# ProtoBoard.net
KiCad netlist of a schematic drawn in Altium Designer
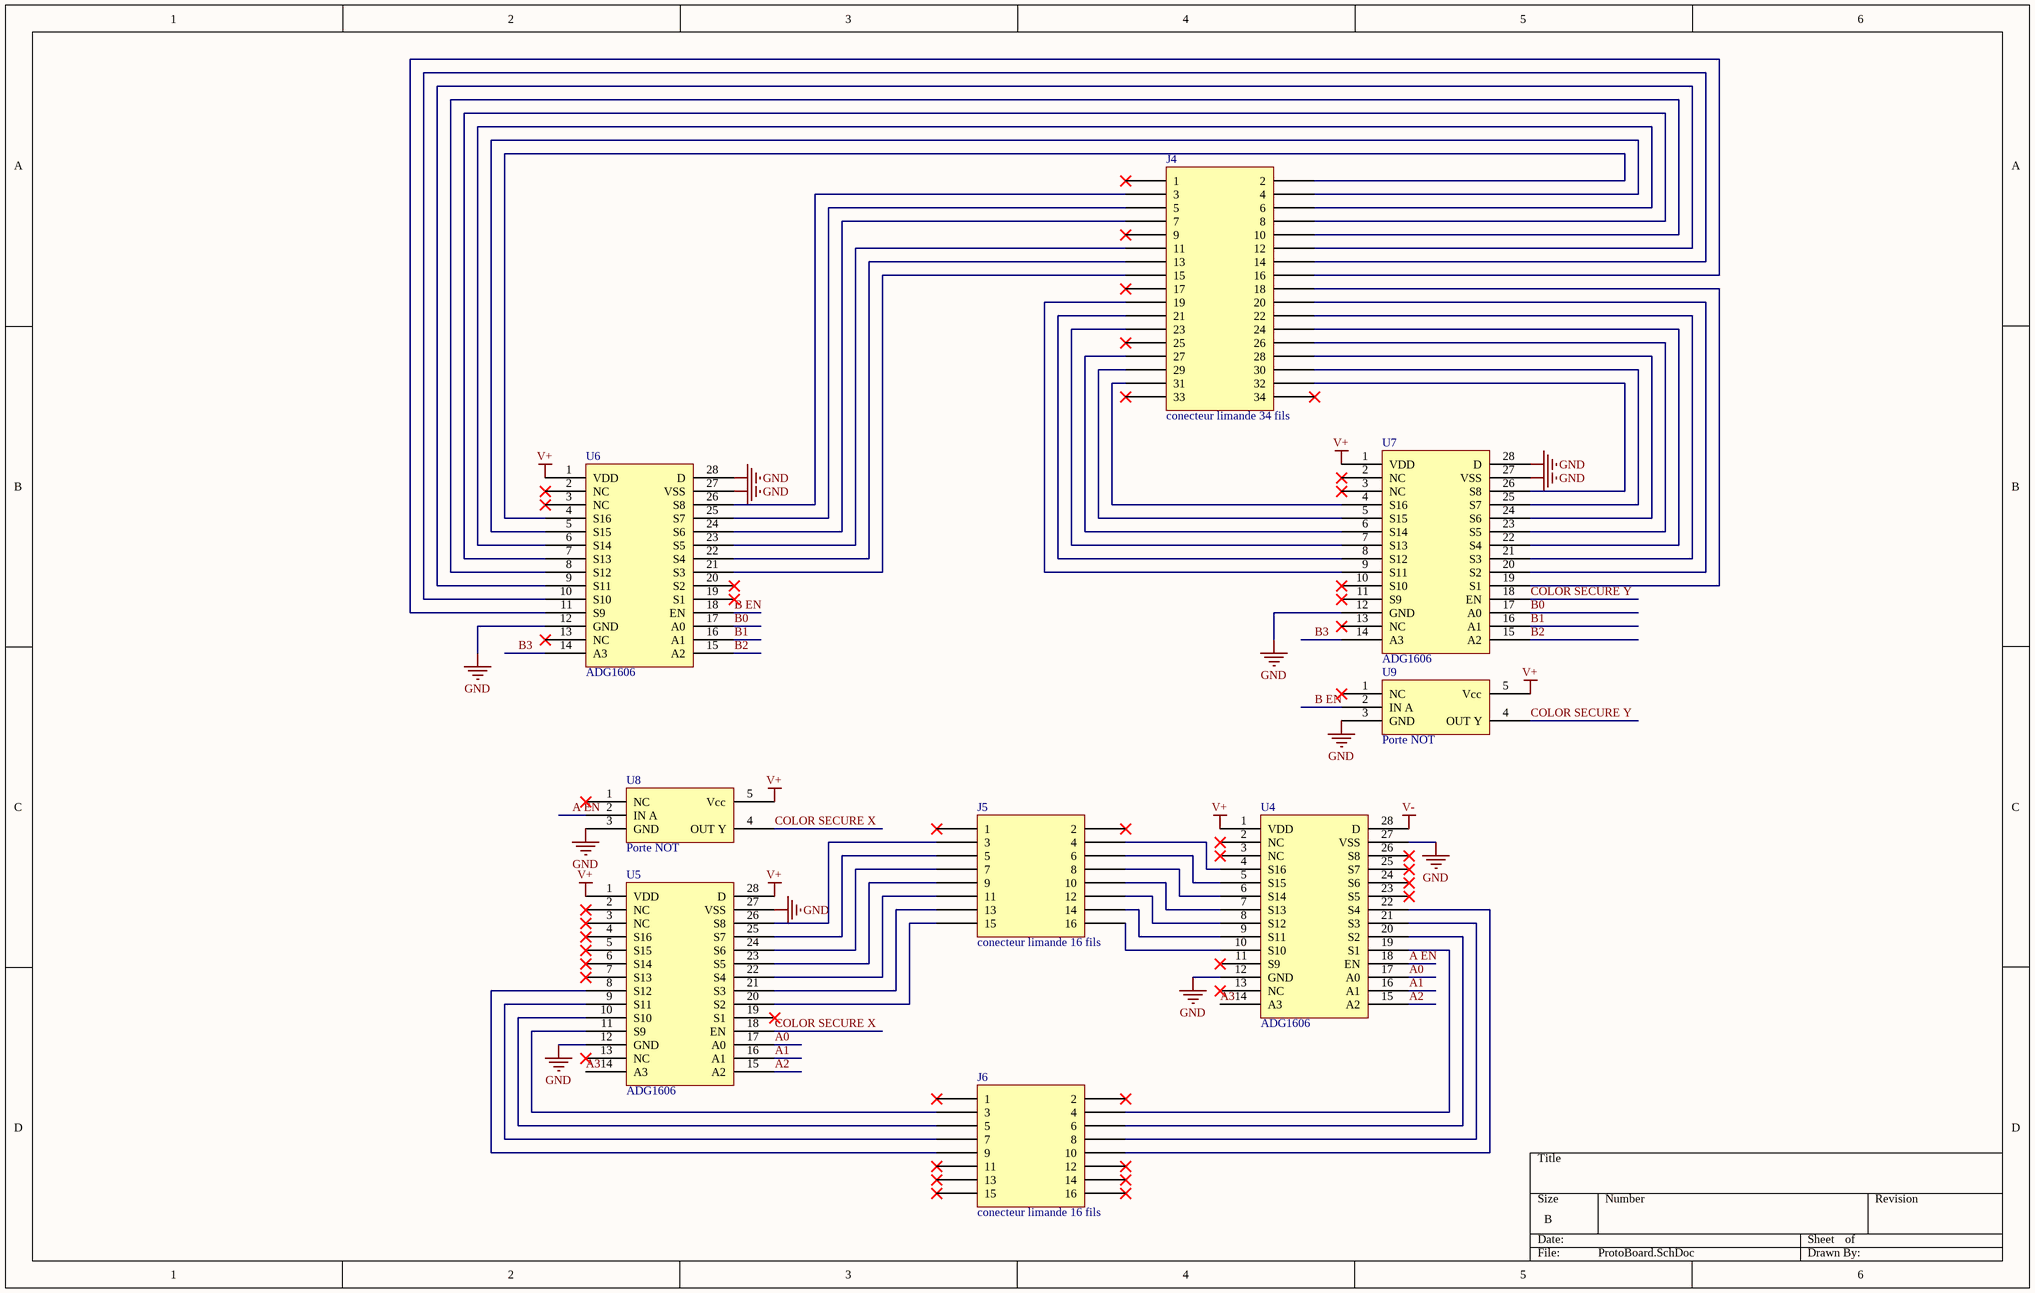
[diagram p0: ProtoBoard.SchDoc]

(export (version "E")
  (design (tool "Eeschema 10.0.6"))
  (components
    (comp (ref "J4")
      (value "conecteur limande 34 fils")
      (footprint "HTSS-117-01-T-DV-P-TR Connecteur 34 pins")
      (libsource (lib "lib_protoboard") (part "Limande 34 fils"))
    )
    (comp (ref "J5")
      (value "conecteur limande 16 fils")
      (footprint "M80-8541642 connecteur 16 pins")
      (libsource (lib "lib_protoboard") (part "Connecteur carte a carte"))
    )
    (comp (ref "J6")
      (value "conecteur limande 16 fils")
      (footprint "M80-8541642 connecteur 16 pins")
      (libsource (lib "lib_protoboard") (part "Connecteur carte a carte"))
    )
    (comp (ref "U4")
      (value "ADG1606")
      (footprint "TSOP65P640X120-28N")
      (libsource (lib "ADG1606") (part "Component_1"))
    )
    (comp (ref "U5")
      (value "ADG1606")
      (footprint "TSOP65P640X120-28N")
      (libsource (lib "ADG1606") (part "Component_1"))
    )
    (comp (ref "U6")
      (value "ADG1606")
      (footprint "TSOP65P640X120-28N")
      (libsource (lib "lib_protoboard") (part "ADG1606"))
    )
    (comp (ref "U7")
      (value "ADG1606")
      (footprint "TSOP65P640X120-28N")
      (libsource (lib "lib_protoboard") (part "ADG1606"))
    )
    (comp (ref "U8")
      (value "Porte NOT")
      (footprint "SOT65P210X110-5N")
      (libsource (lib "lib_protoboard") (part "Porte NOT"))
    )
    (comp (ref "U9")
      (value "Porte NOT")
      (footprint "SOT65P210X110-5N")
      (libsource (lib "lib_protoboard") (part "Porte NOT"))
    )
  )
  (nets
    (net (code "1") (name "/A EN") (class "Default")
      (node (ref "U4") (pin "18") (pinfunction "EN_18") (pintype "passive"))
      (node (ref "U8") (pin "2") (pinfunction "IN_A_2") (pintype "passive"))
    )
    (net (code "2") (name "/A0") (class "Default")
      (node (ref "U4") (pin "17") (pinfunction "A0_17") (pintype "passive"))
      (node (ref "U5") (pin "17") (pinfunction "A0_17") (pintype "passive"))
    )
    (net (code "3") (name "/A1") (class "Default")
      (node (ref "U4") (pin "16") (pinfunction "A1_16") (pintype "passive"))
      (node (ref "U5") (pin "16") (pinfunction "A1_16") (pintype "passive"))
    )
    (net (code "4") (name "/A2") (class "Default")
      (node (ref "U4") (pin "15") (pinfunction "A2_15") (pintype "passive"))
      (node (ref "U5") (pin "15") (pinfunction "A2_15") (pintype "passive"))
    )
    (net (code "5") (name "/A3") (class "Default")
      (node (ref "U4") (pin "14") (pinfunction "A3_14") (pintype "passive"))
      (node (ref "U5") (pin "14") (pinfunction "A3_14") (pintype "passive"))
    )
    (net (code "6") (name "/B EN") (class "Default")
      (node (ref "U6") (pin "18") (pinfunction "EN_18") (pintype "passive"))
      (node (ref "U9") (pin "2") (pinfunction "IN_A_2") (pintype "passive"))
    )
    (net (code "7") (name "/B0") (class "Default")
      (node (ref "U6") (pin "17") (pinfunction "A0_17") (pintype "passive"))
      (node (ref "U7") (pin "17") (pinfunction "A0_17") (pintype "passive"))
    )
    (net (code "8") (name "/B1") (class "Default")
      (node (ref "U6") (pin "16") (pinfunction "A1_16") (pintype "passive"))
      (node (ref "U7") (pin "16") (pinfunction "A1_16") (pintype "passive"))
    )
    (net (code "9") (name "/B2") (class "Default")
      (node (ref "U6") (pin "15") (pinfunction "A2_15") (pintype "passive"))
      (node (ref "U7") (pin "15") (pinfunction "A2_15") (pintype "passive"))
    )
    (net (code "10") (name "/B3") (class "Default")
      (node (ref "U6") (pin "14") (pinfunction "A3_14") (pintype "passive"))
      (node (ref "U7") (pin "14") (pinfunction "A3_14") (pintype "passive"))
    )
    (net (code "11") (name "/COLOR SECURE X") (class "Default")
      (node (ref "U5") (pin "18") (pinfunction "EN_18") (pintype "passive"))
      (node (ref "U8") (pin "4") (pinfunction "OUT_Y_4") (pintype "passive"))
    )
    (net (code "12") (name "/COLOR SECURE Y") (class "Default")
      (node (ref "U7") (pin "18") (pinfunction "EN_18") (pintype "passive"))
      (node (ref "U9") (pin "4") (pinfunction "OUT_Y_4") (pintype "passive"))
    )
    (net (code "13") (name "GND") (class "Default")
      (node (ref "U4") (pin "12") (pinfunction "GND_12") (pintype "passive"))
      (node (ref "U4") (pin "27") (pinfunction "VSS_27") (pintype "passive"))
      (node (ref "U5") (pin "12") (pinfunction "GND_12") (pintype "passive"))
      (node (ref "U5") (pin "27") (pinfunction "VSS_27") (pintype "passive"))
      (node (ref "U6") (pin "12") (pinfunction "GND_12") (pintype "passive"))
      (node (ref "U6") (pin "27") (pinfunction "VSS_27") (pintype "passive"))
      (node (ref "U6") (pin "28") (pinfunction "D_28") (pintype "passive"))
      (node (ref "U7") (pin "12") (pinfunction "GND_12") (pintype "passive"))
      (node (ref "U7") (pin "27") (pinfunction "VSS_27") (pintype "passive"))
      (node (ref "U7") (pin "28") (pinfunction "D_28") (pintype "passive"))
      (node (ref "U8") (pin "3") (pinfunction "GND_3") (pintype "passive"))
      (node (ref "U9") (pin "3") (pinfunction "GND_3") (pintype "passive"))
    )
    (net (code "14") (name "Net-(U4-S1)") (class "Default")
      (node (ref "J6") (pin "4") (pinfunction "4_4") (pintype "passive"))
      (node (ref "U4") (pin "19") (pinfunction "S1_19") (pintype "passive"))
    )
    (net (code "15") (name "Net-(U4-S2)") (class "Default")
      (node (ref "J6") (pin "6") (pinfunction "6_6") (pintype "passive"))
      (node (ref "U4") (pin "20") (pinfunction "S2_20") (pintype "passive"))
    )
    (net (code "16") (name "Net-(U4-S3)") (class "Default")
      (node (ref "J6") (pin "8") (pinfunction "8_8") (pintype "passive"))
      (node (ref "U4") (pin "21") (pinfunction "S3_21") (pintype "passive"))
    )
    (net (code "17") (name "Net-(U4-S4)") (class "Default")
      (node (ref "J6") (pin "10") (pinfunction "10_10") (pintype "passive"))
      (node (ref "U4") (pin "22") (pinfunction "S4_22") (pintype "passive"))
    )
    (net (code "18") (name "Net-(U4-S10)") (class "Default")
      (node (ref "J5") (pin "16") (pinfunction "16_16") (pintype "passive"))
      (node (ref "U4") (pin "10") (pinfunction "S10_10") (pintype "passive"))
    )
    (net (code "19") (name "Net-(U4-S11)") (class "Default")
      (node (ref "J5") (pin "14") (pinfunction "14_14") (pintype "passive"))
      (node (ref "U4") (pin "9") (pinfunction "S11_9") (pintype "passive"))
    )
    (net (code "20") (name "Net-(U4-S12)") (class "Default")
      (node (ref "J5") (pin "12") (pinfunction "12_12") (pintype "passive"))
      (node (ref "U4") (pin "8") (pinfunction "S12_8") (pintype "passive"))
    )
    (net (code "21") (name "Net-(U4-S13)") (class "Default")
      (node (ref "J5") (pin "10") (pinfunction "10_10") (pintype "passive"))
      (node (ref "U4") (pin "7") (pinfunction "S13_7") (pintype "passive"))
    )
    (net (code "22") (name "Net-(U4-S14)") (class "Default")
      (node (ref "J5") (pin "8") (pinfunction "8_8") (pintype "passive"))
      (node (ref "U4") (pin "6") (pinfunction "S14_6") (pintype "passive"))
    )
    (net (code "23") (name "Net-(U4-S15)") (class "Default")
      (node (ref "J5") (pin "6") (pinfunction "6_6") (pintype "passive"))
      (node (ref "U4") (pin "5") (pinfunction "S15_5") (pintype "passive"))
    )
    (net (code "24") (name "Net-(U4-S16)") (class "Default")
      (node (ref "J5") (pin "4") (pinfunction "4_4") (pintype "passive"))
      (node (ref "U4") (pin "4") (pinfunction "S16_4") (pintype "passive"))
    )
    (net (code "25") (name "Net-(U5-S2)") (class "Default")
      (node (ref "J5") (pin "15") (pinfunction "15_15") (pintype "passive"))
      (node (ref "U5") (pin "20") (pinfunction "S2_20") (pintype "passive"))
    )
    (net (code "26") (name "Net-(U5-S3)") (class "Default")
      (node (ref "J5") (pin "13") (pinfunction "13_13") (pintype "passive"))
      (node (ref "U5") (pin "21") (pinfunction "S3_21") (pintype "passive"))
    )
    (net (code "27") (name "Net-(U5-S4)") (class "Default")
      (node (ref "J5") (pin "11") (pinfunction "11_11") (pintype "passive"))
      (node (ref "U5") (pin "22") (pinfunction "S4_22") (pintype "passive"))
    )
    (net (code "28") (name "Net-(U5-S5)") (class "Default")
      (node (ref "J5") (pin "9") (pinfunction "9_9") (pintype "passive"))
      (node (ref "U5") (pin "23") (pinfunction "S5_23") (pintype "passive"))
    )
    (net (code "29") (name "Net-(U5-S6)") (class "Default")
      (node (ref "J5") (pin "7") (pinfunction "7_7") (pintype "passive"))
      (node (ref "U5") (pin "24") (pinfunction "S6_24") (pintype "passive"))
    )
    (net (code "30") (name "Net-(U5-S7)") (class "Default")
      (node (ref "J5") (pin "5") (pinfunction "5_5") (pintype "passive"))
      (node (ref "U5") (pin "25") (pinfunction "S7_25") (pintype "passive"))
    )
    (net (code "31") (name "Net-(U5-S8)") (class "Default")
      (node (ref "J5") (pin "3") (pinfunction "3_3") (pintype "passive"))
      (node (ref "U5") (pin "26") (pinfunction "S8_26") (pintype "passive"))
    )
    (net (code "32") (name "Net-(U5-S9)") (class "Default")
      (node (ref "J6") (pin "3") (pinfunction "3_3") (pintype "passive"))
      (node (ref "U5") (pin "11") (pinfunction "S9_11") (pintype "passive"))
    )
    (net (code "33") (name "Net-(U5-S10)") (class "Default")
      (node (ref "J6") (pin "5") (pinfunction "5_5") (pintype "passive"))
      (node (ref "U5") (pin "10") (pinfunction "S10_10") (pintype "passive"))
    )
    (net (code "34") (name "Net-(U5-S11)") (class "Default")
      (node (ref "J6") (pin "7") (pinfunction "7_7") (pintype "passive"))
      (node (ref "U5") (pin "9") (pinfunction "S11_9") (pintype "passive"))
    )
    (net (code "35") (name "Net-(U5-S12)") (class "Default")
      (node (ref "J6") (pin "9") (pinfunction "9_9") (pintype "passive"))
      (node (ref "U5") (pin "8") (pinfunction "S12_8") (pintype "passive"))
    )
    (net (code "36") (name "Net-(U6-S3)") (class "Default")
      (node (ref "J4") (pin "15") (pinfunction "15_15") (pintype "passive"))
      (node (ref "U6") (pin "21") (pinfunction "S3_21") (pintype "passive"))
    )
    (net (code "37") (name "Net-(U6-S4)") (class "Default")
      (node (ref "J4") (pin "13") (pinfunction "13_13") (pintype "passive"))
      (node (ref "U6") (pin "22") (pinfunction "S4_22") (pintype "passive"))
    )
    (net (code "38") (name "Net-(U6-S5)") (class "Default")
      (node (ref "J4") (pin "11") (pinfunction "11_11") (pintype "passive"))
      (node (ref "U6") (pin "23") (pinfunction "S5_23") (pintype "passive"))
    )
    (net (code "39") (name "Net-(U6-S6)") (class "Default")
      (node (ref "J4") (pin "7") (pinfunction "7_7") (pintype "passive"))
      (node (ref "U6") (pin "24") (pinfunction "S6_24") (pintype "passive"))
    )
    (net (code "40") (name "Net-(U6-S7)") (class "Default")
      (node (ref "J4") (pin "5") (pinfunction "5_5") (pintype "passive"))
      (node (ref "U6") (pin "25") (pinfunction "S7_25") (pintype "passive"))
    )
    (net (code "41") (name "Net-(U6-S8)") (class "Default")
      (node (ref "J4") (pin "3") (pinfunction "3_3") (pintype "passive"))
      (node (ref "U6") (pin "26") (pinfunction "S8_26") (pintype "passive"))
    )
    (net (code "42") (name "Net-(U6-S9)") (class "Default")
      (node (ref "J4") (pin "16") (pinfunction "16_16") (pintype "passive"))
      (node (ref "U6") (pin "11") (pinfunction "S9_11") (pintype "passive"))
    )
    (net (code "43") (name "Net-(U6-S10)") (class "Default")
      (node (ref "J4") (pin "14") (pinfunction "14_14") (pintype "passive"))
      (node (ref "U6") (pin "10") (pinfunction "S10_10") (pintype "passive"))
    )
    (net (code "44") (name "Net-(U6-S11)") (class "Default")
      (node (ref "J4") (pin "12") (pinfunction "12_12") (pintype "passive"))
      (node (ref "U6") (pin "9") (pinfunction "S11_9") (pintype "passive"))
    )
    (net (code "45") (name "Net-(U6-S12)") (class "Default")
      (node (ref "J4") (pin "10") (pinfunction "10_10") (pintype "passive"))
      (node (ref "U6") (pin "8") (pinfunction "S12_8") (pintype "passive"))
    )
    (net (code "46") (name "Net-(U6-S13)") (class "Default")
      (node (ref "J4") (pin "8") (pinfunction "8_8") (pintype "passive"))
      (node (ref "U6") (pin "7") (pinfunction "S13_7") (pintype "passive"))
    )
    (net (code "47") (name "Net-(U6-S14)") (class "Default")
      (node (ref "J4") (pin "6") (pinfunction "6_6") (pintype "passive"))
      (node (ref "U6") (pin "6") (pinfunction "S14_6") (pintype "passive"))
    )
    (net (code "48") (name "Net-(U6-S15)") (class "Default")
      (node (ref "J4") (pin "4") (pinfunction "4_4") (pintype "passive"))
      (node (ref "U6") (pin "5") (pinfunction "S15_5") (pintype "passive"))
    )
    (net (code "49") (name "Net-(U6-S16)") (class "Default")
      (node (ref "J4") (pin "2") (pinfunction "2_2") (pintype "passive"))
      (node (ref "U6") (pin "4") (pinfunction "S16_4") (pintype "passive"))
    )
    (net (code "50") (name "Net-(U7-S1)") (class "Default")
      (node (ref "J4") (pin "18") (pinfunction "18_18") (pintype "passive"))
      (node (ref "U7") (pin "19") (pinfunction "S1_19") (pintype "passive"))
    )
    (net (code "51") (name "Net-(U7-S2)") (class "Default")
      (node (ref "J4") (pin "20") (pinfunction "20_20") (pintype "passive"))
      (node (ref "U7") (pin "20") (pinfunction "S2_20") (pintype "passive"))
    )
    (net (code "52") (name "Net-(U7-S3)") (class "Default")
      (node (ref "J4") (pin "22") (pinfunction "22_22") (pintype "passive"))
      (node (ref "U7") (pin "21") (pinfunction "S3_21") (pintype "passive"))
    )
    (net (code "53") (name "Net-(U7-S4)") (class "Default")
      (node (ref "J4") (pin "24") (pinfunction "24_24") (pintype "passive"))
      (node (ref "U7") (pin "22") (pinfunction "S4_22") (pintype "passive"))
    )
    (net (code "54") (name "Net-(U7-S5)") (class "Default")
      (node (ref "J4") (pin "26") (pinfunction "26_26") (pintype "passive"))
      (node (ref "U7") (pin "23") (pinfunction "S5_23") (pintype "passive"))
    )
    (net (code "55") (name "Net-(U7-S6)") (class "Default")
      (node (ref "J4") (pin "28") (pinfunction "28_28") (pintype "passive"))
      (node (ref "U7") (pin "24") (pinfunction "S6_24") (pintype "passive"))
    )
    (net (code "56") (name "Net-(U7-S7)") (class "Default")
      (node (ref "J4") (pin "30") (pinfunction "30_30") (pintype "passive"))
      (node (ref "U7") (pin "25") (pinfunction "S7_25") (pintype "passive"))
    )
    (net (code "57") (name "Net-(U7-S8)") (class "Default")
      (node (ref "J4") (pin "32") (pinfunction "32_32") (pintype "passive"))
      (node (ref "U7") (pin "26") (pinfunction "S8_26") (pintype "passive"))
    )
    (net (code "58") (name "Net-(U7-S11)") (class "Default")
      (node (ref "J4") (pin "19") (pinfunction "19_19") (pintype "passive"))
      (node (ref "U7") (pin "9") (pinfunction "S11_9") (pintype "passive"))
    )
    (net (code "59") (name "Net-(U7-S12)") (class "Default")
      (node (ref "J4") (pin "21") (pinfunction "21_21") (pintype "passive"))
      (node (ref "U7") (pin "8") (pinfunction "S12_8") (pintype "passive"))
    )
    (net (code "60") (name "Net-(U7-S13)") (class "Default")
      (node (ref "J4") (pin "23") (pinfunction "23_23") (pintype "passive"))
      (node (ref "U7") (pin "7") (pinfunction "S13_7") (pintype "passive"))
    )
    (net (code "61") (name "Net-(U7-S14)") (class "Default")
      (node (ref "J4") (pin "27") (pinfunction "27_27") (pintype "passive"))
      (node (ref "U7") (pin "6") (pinfunction "S14_6") (pintype "passive"))
    )
    (net (code "62") (name "Net-(U7-S15)") (class "Default")
      (node (ref "J4") (pin "29") (pinfunction "29_29") (pintype "passive"))
      (node (ref "U7") (pin "5") (pinfunction "S15_5") (pintype "passive"))
    )
    (net (code "63") (name "Net-(U7-S16)") (class "Default")
      (node (ref "J4") (pin "31") (pinfunction "31_31") (pintype "passive"))
      (node (ref "U7") (pin "4") (pinfunction "S16_4") (pintype "passive"))
    )
    (net (code "64") (name "V+") (class "Default")
      (node (ref "U4") (pin "1") (pinfunction "VDD_1") (pintype "passive"))
      (node (ref "U5") (pin "1") (pinfunction "VDD_1") (pintype "passive"))
      (node (ref "U5") (pin "28") (pinfunction "D_28") (pintype "passive"))
      (node (ref "U6") (pin "1") (pinfunction "VDD_1") (pintype "passive"))
      (node (ref "U7") (pin "1") (pinfunction "VDD_1") (pintype "passive"))
      (node (ref "U8") (pin "5") (pinfunction "Vcc_5") (pintype "passive"))
      (node (ref "U9") (pin "5") (pinfunction "Vcc_5") (pintype "passive"))
    )
    (net (code "65") (name "V-") (class "Default")
      (node (ref "U4") (pin "28") (pinfunction "D_28") (pintype "passive"))
    )
    (net (code "66") (name "unconnected-(J4-Pad1)") (class "Default")
      (node (ref "J4") (pin "1") (pinfunction "1_1") (pintype "passive+no_connect"))
    )
    (net (code "67") (name "unconnected-(J4-Pad9)") (class "Default")
      (node (ref "J4") (pin "9") (pinfunction "9_9") (pintype "passive+no_connect"))
    )
    (net (code "68") (name "unconnected-(J4-Pad17)") (class "Default")
      (node (ref "J4") (pin "17") (pinfunction "17_17") (pintype "passive+no_connect"))
    )
    (net (code "69") (name "unconnected-(J4-Pad25)") (class "Default")
      (node (ref "J4") (pin "25") (pinfunction "25_25") (pintype "passive+no_connect"))
    )
    (net (code "70") (name "unconnected-(J4-Pad33)") (class "Default")
      (node (ref "J4") (pin "33") (pinfunction "33_33") (pintype "passive+no_connect"))
    )
    (net (code "71") (name "unconnected-(J4-Pad34)") (class "Default")
      (node (ref "J4") (pin "34") (pinfunction "34_34") (pintype "passive+no_connect"))
    )
    (net (code "72") (name "unconnected-(J5-Pad1)") (class "Default")
      (node (ref "J5") (pin "1") (pinfunction "1_1") (pintype "passive+no_connect"))
    )
    (net (code "73") (name "unconnected-(J5-Pad2)") (class "Default")
      (node (ref "J5") (pin "2") (pinfunction "2_2") (pintype "passive+no_connect"))
    )
    (net (code "74") (name "unconnected-(J6-Pad1)") (class "Default")
      (node (ref "J6") (pin "1") (pinfunction "1_1") (pintype "passive+no_connect"))
    )
    (net (code "75") (name "unconnected-(J6-Pad2)") (class "Default")
      (node (ref "J6") (pin "2") (pinfunction "2_2") (pintype "passive+no_connect"))
    )
    (net (code "76") (name "unconnected-(J6-Pad11)") (class "Default")
      (node (ref "J6") (pin "11") (pinfunction "11_11") (pintype "passive+no_connect"))
    )
    (net (code "77") (name "unconnected-(J6-Pad12)") (class "Default")
      (node (ref "J6") (pin "12") (pinfunction "12_12") (pintype "passive+no_connect"))
    )
    (net (code "78") (name "unconnected-(J6-Pad13)") (class "Default")
      (node (ref "J6") (pin "13") (pinfunction "13_13") (pintype "passive+no_connect"))
    )
    (net (code "79") (name "unconnected-(J6-Pad14)") (class "Default")
      (node (ref "J6") (pin "14") (pinfunction "14_14") (pintype "passive+no_connect"))
    )
    (net (code "80") (name "unconnected-(J6-Pad15)") (class "Default")
      (node (ref "J6") (pin "15") (pinfunction "15_15") (pintype "passive+no_connect"))
    )
    (net (code "81") (name "unconnected-(J6-Pad16)") (class "Default")
      (node (ref "J6") (pin "16") (pinfunction "16_16") (pintype "passive+no_connect"))
    )
    (net (code "82") (name "unconnected-(U4-NC-Pad2)") (class "Default")
      (node (ref "U4") (pin "2") (pinfunction "NC_2") (pintype "passive+no_connect"))
    )
    (net (code "83") (name "unconnected-(U4-NC-Pad3)") (class "Default")
      (node (ref "U4") (pin "3") (pinfunction "NC_3") (pintype "passive+no_connect"))
    )
    (net (code "84") (name "unconnected-(U4-NC-Pad13)") (class "Default")
      (node (ref "U4") (pin "13") (pinfunction "NC_13") (pintype "passive+no_connect"))
    )
    (net (code "85") (name "unconnected-(U4-S5-Pad23)") (class "Default")
      (node (ref "U4") (pin "23") (pinfunction "S5_23") (pintype "passive+no_connect"))
    )
    (net (code "86") (name "unconnected-(U4-S6-Pad24)") (class "Default")
      (node (ref "U4") (pin "24") (pinfunction "S6_24") (pintype "passive+no_connect"))
    )
    (net (code "87") (name "unconnected-(U4-S7-Pad25)") (class "Default")
      (node (ref "U4") (pin "25") (pinfunction "S7_25") (pintype "passive+no_connect"))
    )
    (net (code "88") (name "unconnected-(U4-S8-Pad26)") (class "Default")
      (node (ref "U4") (pin "26") (pinfunction "S8_26") (pintype "passive+no_connect"))
    )
    (net (code "89") (name "unconnected-(U4-S9-Pad11)") (class "Default")
      (node (ref "U4") (pin "11") (pinfunction "S9_11") (pintype "passive+no_connect"))
    )
    (net (code "90") (name "unconnected-(U5-NC-Pad2)") (class "Default")
      (node (ref "U5") (pin "2") (pinfunction "NC_2") (pintype "passive+no_connect"))
    )
    (net (code "91") (name "unconnected-(U5-NC-Pad3)") (class "Default")
      (node (ref "U5") (pin "3") (pinfunction "NC_3") (pintype "passive+no_connect"))
    )
    (net (code "92") (name "unconnected-(U5-NC-Pad13)") (class "Default")
      (node (ref "U5") (pin "13") (pinfunction "NC_13") (pintype "passive+no_connect"))
    )
    (net (code "93") (name "unconnected-(U5-S1-Pad19)") (class "Default")
      (node (ref "U5") (pin "19") (pinfunction "S1_19") (pintype "passive+no_connect"))
    )
    (net (code "94") (name "unconnected-(U5-S13-Pad7)") (class "Default")
      (node (ref "U5") (pin "7") (pinfunction "S13_7") (pintype "passive+no_connect"))
    )
    (net (code "95") (name "unconnected-(U5-S14-Pad6)") (class "Default")
      (node (ref "U5") (pin "6") (pinfunction "S14_6") (pintype "passive+no_connect"))
    )
    (net (code "96") (name "unconnected-(U5-S15-Pad5)") (class "Default")
      (node (ref "U5") (pin "5") (pinfunction "S15_5") (pintype "passive+no_connect"))
    )
    (net (code "97") (name "unconnected-(U5-S16-Pad4)") (class "Default")
      (node (ref "U5") (pin "4") (pinfunction "S16_4") (pintype "passive+no_connect"))
    )
    (net (code "98") (name "unconnected-(U6-NC-Pad2)") (class "Default")
      (node (ref "U6") (pin "2") (pinfunction "NC_2") (pintype "passive+no_connect"))
    )
    (net (code "99") (name "unconnected-(U6-NC-Pad3)") (class "Default")
      (node (ref "U6") (pin "3") (pinfunction "NC_3") (pintype "passive+no_connect"))
    )
    (net (code "100") (name "unconnected-(U6-NC-Pad13)") (class "Default")
      (node (ref "U6") (pin "13") (pinfunction "NC_13") (pintype "passive+no_connect"))
    )
    (net (code "101") (name "unconnected-(U6-S1-Pad19)") (class "Default")
      (node (ref "U6") (pin "19") (pinfunction "S1_19") (pintype "passive+no_connect"))
    )
    (net (code "102") (name "unconnected-(U6-S2-Pad20)") (class "Default")
      (node (ref "U6") (pin "20") (pinfunction "S2_20") (pintype "passive+no_connect"))
    )
    (net (code "103") (name "unconnected-(U7-NC-Pad2)") (class "Default")
      (node (ref "U7") (pin "2") (pinfunction "NC_2") (pintype "passive+no_connect"))
    )
    (net (code "104") (name "unconnected-(U7-NC-Pad3)") (class "Default")
      (node (ref "U7") (pin "3") (pinfunction "NC_3") (pintype "passive+no_connect"))
    )
    (net (code "105") (name "unconnected-(U7-NC-Pad13)") (class "Default")
      (node (ref "U7") (pin "13") (pinfunction "NC_13") (pintype "passive+no_connect"))
    )
    (net (code "106") (name "unconnected-(U7-S9-Pad11)") (class "Default")
      (node (ref "U7") (pin "11") (pinfunction "S9_11") (pintype "passive+no_connect"))
    )
    (net (code "107") (name "unconnected-(U7-S10-Pad10)") (class "Default")
      (node (ref "U7") (pin "10") (pinfunction "S10_10") (pintype "passive+no_connect"))
    )
    (net (code "108") (name "unconnected-(U8-NC-Pad1)") (class "Default")
      (node (ref "U8") (pin "1") (pinfunction "NC_1") (pintype "passive+no_connect"))
    )
    (net (code "109") (name "unconnected-(U9-NC-Pad1)") (class "Default")
      (node (ref "U9") (pin "1") (pinfunction "NC_1") (pintype "passive+no_connect"))
    )
  )
)
